# SparkFun_TC78H670FTG_Breakout.net
KiCad netlist of a schematic drawn in EAGLE
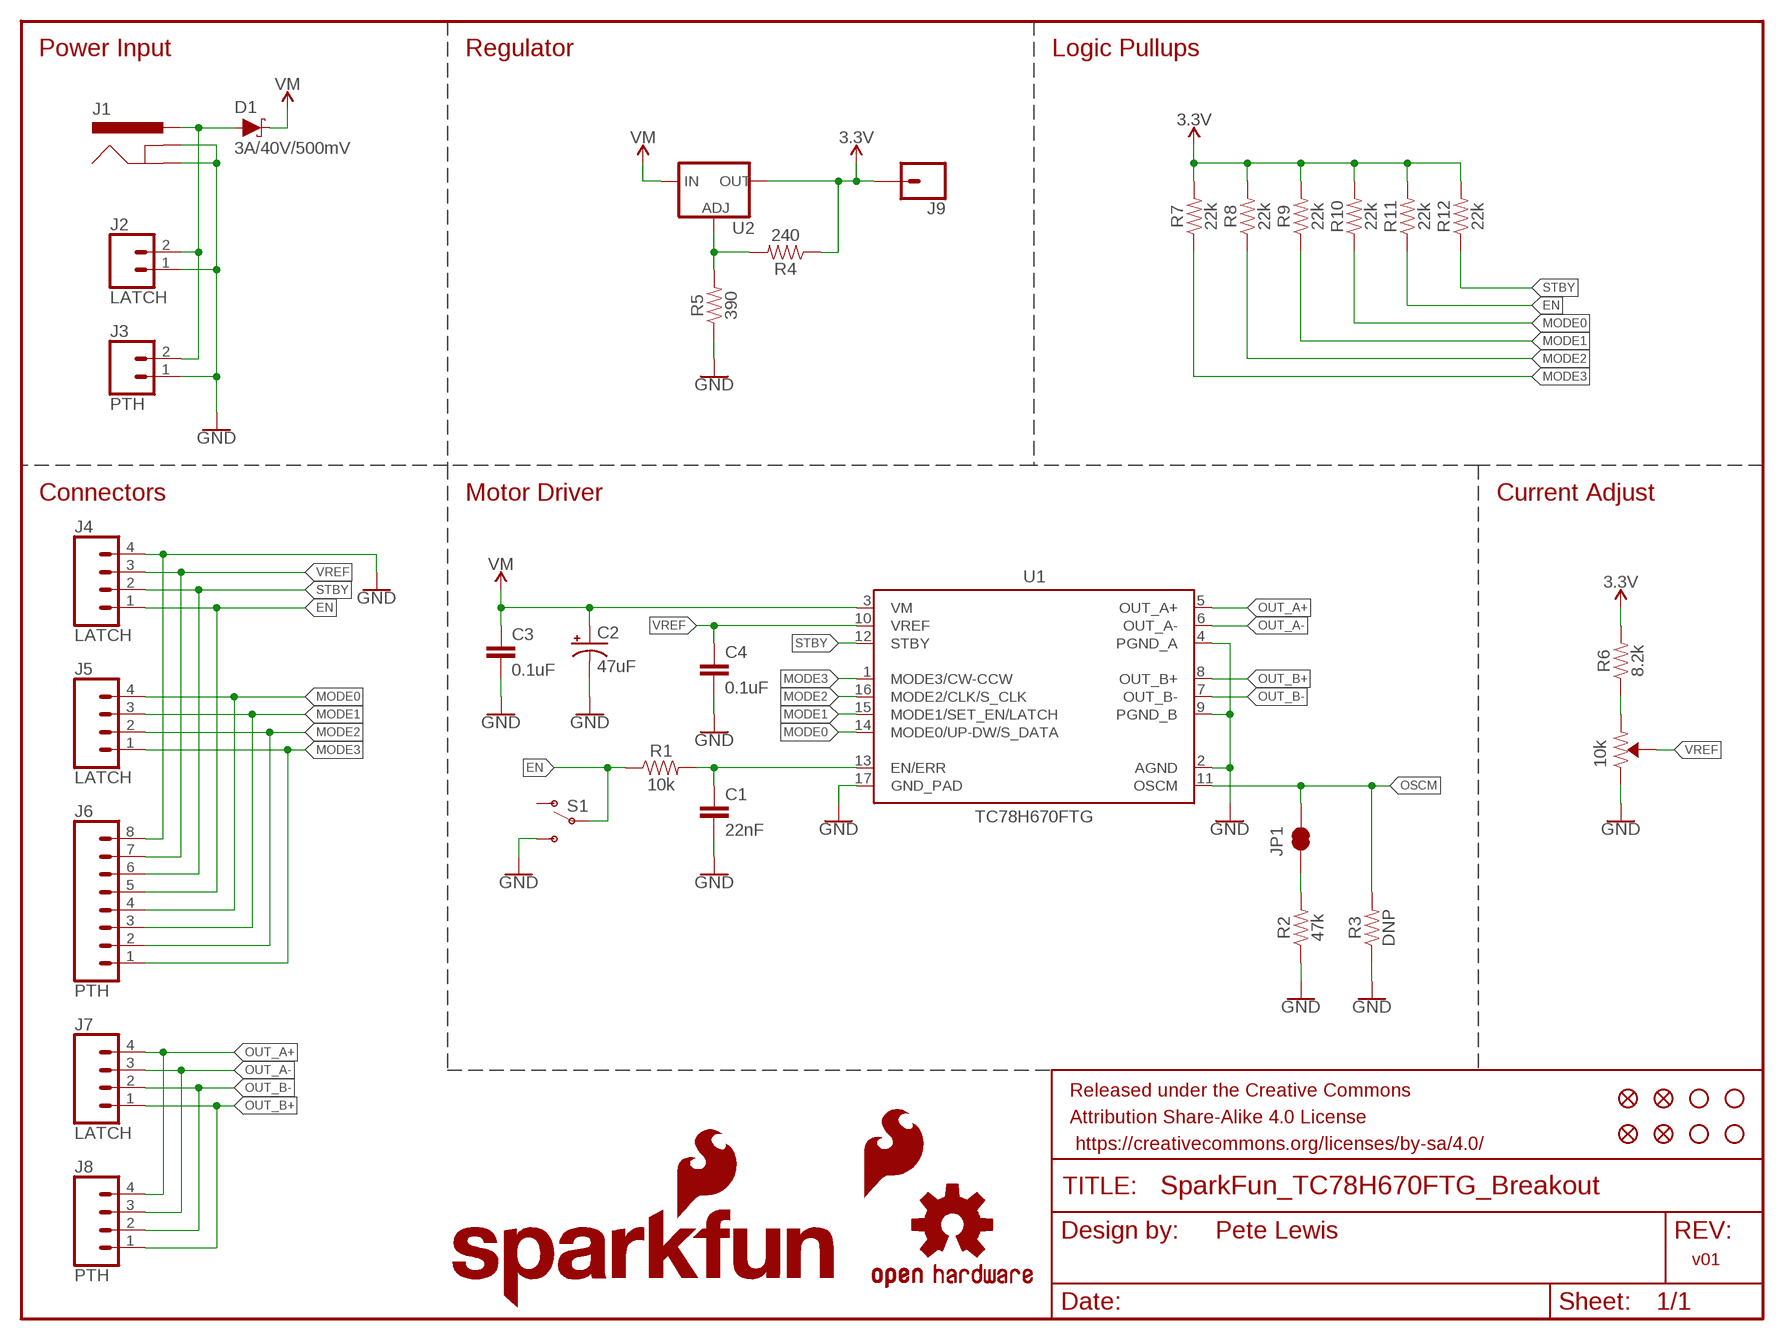
[diagram p0: schematic, sheet 1]

(export (version "E")
  (design (tool "Eeschema 10.0.6"))
  (components
    (comp (ref "C1")
      (value "22nF")
      (footprint "eagle-import:0603")
      (libsource (lib "eagle-import") (part "22NF/22,000PF-0603-50V-10%"))
    )
    (comp (ref "C2")
      (value "47uF")
      (footprint "eagle-import:PANASONIC_D")
      (libsource (lib "eagle-import") (part "47UF-POLAR-PANASONIC_D-35V-20%"))
    )
    (comp (ref "C3")
      (value "0.1uF")
      (footprint "eagle-import:0603")
      (libsource (lib "eagle-import") (part "0.1UF-0603-25V-(+80/-20%)"))
    )
    (comp (ref "C4")
      (value "0.1uF")
      (footprint "eagle-import:0603")
      (libsource (lib "eagle-import") (part "0.1UF-0603-25V-(+80/-20%)"))
    )
    (comp (ref "D1")
      (value "3A/40V/500mV")
      (footprint "eagle-import:SMA-DIODE")
      (libsource (lib "eagle-import") (part "DIODE-SCHOTTKY-B340A"))
    )
    (comp (ref "FID1")
      (value "FIDUCIAL1X2")
      (footprint "eagle-import:FIDUCIAL-1X2")
      (libsource (lib "eagle-import") (part "FIDUCIAL1X2"))
    )
    (comp (ref "FID2")
      (value "FIDUCIAL1X2")
      (footprint "eagle-import:FIDUCIAL-1X2")
      (libsource (lib "eagle-import") (part "FIDUCIAL1X2"))
    )
    (comp (ref "FID3")
      (value "FIDUCIAL1X2")
      (footprint "eagle-import:FIDUCIAL-1X2")
      (libsource (lib "eagle-import") (part "FIDUCIAL1X2"))
    )
    (comp (ref "FID4")
      (value "FIDUCIAL1X2")
      (footprint "eagle-import:FIDUCIAL-1X2")
      (libsource (lib "eagle-import") (part "FIDUCIAL1X2"))
    )
    (comp (ref "FRAME1")
      (value "FRAME-LETTER")
      (footprint "eagle-import:CREATIVE_COMMONS")
      (libsource (lib "eagle-import") (part "FRAME-LETTER"))
    )
    (comp (ref "J1")
      (value "POWER_JACKTOE")
      (footprint "eagle-import:POWER_JACK_SMD_OVERPASTE_TOE")
      (libsource (lib "eagle-import") (part "POWER_JACKTOE"))
    )
    (comp (ref "J2")
      (value "LATCH")
      (footprint "eagle-import:LATCHTERMINAL-5MM-2")
      (libsource (lib "eagle-import") (part "CONN_02LATCH_2"))
    )
    (comp (ref "J3")
      (value "PTH")
      (footprint "eagle-import:1X02_NO_SILK")
      (libsource (lib "eagle-import") (part "CONN_021X02_NO_SILK"))
    )
    (comp (ref "J4")
      (value "LATCH")
      (footprint "eagle-import:LATCHTERMINAL-5MM-4")
      (libsource (lib "eagle-import") (part "CONN_04LATCH"))
    )
    (comp (ref "J5")
      (value "LATCH")
      (footprint "eagle-import:LATCHTERMINAL-5MM-4")
      (libsource (lib "eagle-import") (part "CONN_04LATCH"))
    )
    (comp (ref "J6")
      (value "PTH")
      (footprint "eagle-import:1X08_NO_SILK")
      (libsource (lib "eagle-import") (part "CONN_08NO_SILK_FEMALE_PTH"))
    )
    (comp (ref "J7")
      (value "LATCH")
      (footprint "eagle-import:LATCHTERMINAL-5MM-4")
      (libsource (lib "eagle-import") (part "CONN_04LATCH"))
    )
    (comp (ref "J8")
      (value "PTH")
      (footprint "eagle-import:1X04_NO_SILK")
      (libsource (lib "eagle-import") (part "CONN_041X04_NO_SILK"))
    )
    (comp (ref "J9")
      (value "CONN_01PTH_NO_SILK_YES_STOP")
      (footprint "eagle-import:1X01_NO_SILK")
      (libsource (lib "eagle-import") (part "CONN_01PTH_NO_SILK_YES_STOP"))
    )
    (comp (ref "JP1")
      (value "JUMPER-SMT_2_NC_TRACE_SILK")
      (footprint "eagle-import:SMT-JUMPER_2_NC_TRACE_SILK")
      (libsource (lib "eagle-import") (part "JUMPER-SMT_2_NC_TRACE_SILK"))
    )
    (comp (ref "LOGO1")
      (value "SFE_LOGO_NAME_FLAME.1_INCH")
      (footprint "eagle-import:SFE_LOGO_NAME_FLAME_.1")
      (libsource (lib "eagle-import") (part "SFE_LOGO_NAME_FLAME.1_INCH"))
    )
    (comp (ref "LOGO2")
      (value "OSHW-LOGOS")
      (footprint "eagle-import:OSHW-LOGO-S")
      (libsource (lib "eagle-import") (part "OSHW-LOGOS"))
    )
    (comp (ref "LOGO4")
      (value "SFE_LOGO_FLAME.1_INCH")
      (footprint "eagle-import:SFE_LOGO_FLAME_.1")
      (libsource (lib "eagle-import") (part "SFE_LOGO_FLAME.1_INCH"))
    )
    (comp (ref "R1")
      (value "10k")
      (footprint "eagle-import:0603")
      (libsource (lib "eagle-import") (part "10KOHM-0603-1/10W-1%"))
    )
    (comp (ref "R2")
      (value "47k")
      (footprint "eagle-import:0603")
      (libsource (lib "eagle-import") (part "47KOHM-0603-1/10W-1%"))
    )
    (comp (ref "R3")
      (value "DNP")
      (footprint "eagle-import:AXIAL-0.3")
      (libsource (lib "eagle-import") (part "RESISTORAXIAL-0.3"))
    )
    (comp (ref "R4")
      (value "240")
      (footprint "eagle-import:0603")
      (libsource (lib "eagle-import") (part "240OHM-0603-1/10W-1%"))
    )
    (comp (ref "R5")
      (value "390")
      (footprint "eagle-import:0603")
      (libsource (lib "eagle-import") (part "390OHM-0603-1/10W-1%"))
    )
    (comp (ref "R6")
      (value "8.2k")
      (footprint "eagle-import:0603")
      (libsource (lib "eagle-import") (part "8.2KOHM-0603-1/10W-5%"))
    )
    (comp (ref "R7")
      (value "22k")
      (footprint "eagle-import:0603")
      (libsource (lib "eagle-import") (part "22KOHM-0603-1/10W-1%"))
    )
    (comp (ref "R8")
      (value "22k")
      (footprint "eagle-import:0603")
      (libsource (lib "eagle-import") (part "22KOHM-0603-1/10W-1%"))
    )
    (comp (ref "R9")
      (value "22k")
      (footprint "eagle-import:0603")
      (libsource (lib "eagle-import") (part "22KOHM-0603-1/10W-1%"))
    )
    (comp (ref "R10")
      (value "22k")
      (footprint "eagle-import:0603")
      (libsource (lib "eagle-import") (part "22KOHM-0603-1/10W-1%"))
    )
    (comp (ref "R11")
      (value "22k")
      (footprint "eagle-import:0603")
      (libsource (lib "eagle-import") (part "22KOHM-0603-1/10W-1%"))
    )
    (comp (ref "R12")
      (value "22k")
      (footprint "eagle-import:0603")
      (libsource (lib "eagle-import") (part "22KOHM-0603-1/10W-1%"))
    )
    (comp (ref "S1")
      (value "SWITCH-SPDT-PTH-11.6X4.0MM-LOCK")
      (footprint "eagle-import:SWITCH_SPDT_PTH_11.6X4.0MM_LOCK")
      (libsource (lib "eagle-import") (part "SWITCH-SPDT-PTH-11.6X4.0MM-LOCK"))
    )
    (comp (ref "STANDOFF1")
      (value "STAND-OFF")
      (footprint "eagle-import:STAND-OFF")
      (libsource (lib "eagle-import") (part "STAND-OFF"))
    )
    (comp (ref "STANDOFF2")
      (value "STAND-OFF")
      (footprint "eagle-import:STAND-OFF")
      (libsource (lib "eagle-import") (part "STAND-OFF"))
    )
    (comp (ref "STANDOFF3")
      (value "STAND-OFF")
      (footprint "eagle-import:STAND-OFF")
      (libsource (lib "eagle-import") (part "STAND-OFF"))
    )
    (comp (ref "STANDOFF4")
      (value "STAND-OFF")
      (footprint "eagle-import:STAND-OFF")
      (libsource (lib "eagle-import") (part "STAND-OFF"))
    )
    (comp (ref "U1")
      (value "TC78H670FTG")
      (footprint "eagle-import:P-VQFN16-0303-0.50-001")
      (libsource (lib "eagle-import") (part "TC78H670FTG"))
    )
    (comp (ref "U2")
      (value "V_REG_LM1117SOT223")
      (footprint "eagle-import:SOT223")
      (libsource (lib "eagle-import") (part "V_REG_LM1117SOT223"))
    )
    (comp (ref "VR1")
      (value "10k")
      (footprint "eagle-import:TRIMPOT-SMD-3MM-CLOSED")
      (libsource (lib "eagle-import") (part "TRIMPOT-SMD-3MM-CLOSED-1/8W-20%"))
    )
  )
  (nets
    (net (code "1") (name "3.3V") (class "Default")
      (node (ref "J9") (pin "1") (pinfunction "1_1") (pintype "passive"))
      (node (ref "R10") (pin "2") (pinfunction "2_2") (pintype "passive"))
      (node (ref "R11") (pin "2") (pinfunction "2_2") (pintype "passive"))
      (node (ref "R12") (pin "2") (pinfunction "2_2") (pintype "passive"))
      (node (ref "R4") (pin "1") (pinfunction "1_1") (pintype "passive"))
      (node (ref "R6") (pin "2") (pinfunction "2_2") (pintype "passive"))
      (node (ref "R7") (pin "2") (pinfunction "2_2") (pintype "passive"))
      (node (ref "R8") (pin "2") (pinfunction "2_2") (pintype "passive"))
      (node (ref "R9") (pin "2") (pinfunction "2_2") (pintype "passive"))
      (node (ref "U2") (pin "2") (pinfunction "OUT_2") (pintype "output"))
      (node (ref "U2") (pin "4") (pinfunction "OUT_4") (pintype "output"))
    )
    (net (code "2") (name "EN") (class "Default")
      (node (ref "J4") (pin "1") (pinfunction "1_1") (pintype "passive"))
      (node (ref "J6") (pin "5") (pinfunction "5_5") (pintype "passive"))
      (node (ref "R1") (pin "1") (pinfunction "1_1") (pintype "passive"))
      (node (ref "R11") (pin "1") (pinfunction "1_1") (pintype "passive"))
      (node (ref "S1") (pin "2") (pinfunction "P_2") (pintype "passive"))
    )
    (net (code "3") (name "GND") (class "Default")
      (node (ref "C1") (pin "2") (pinfunction "2_2") (pintype "passive"))
      (node (ref "C2") (pin "-") (pinfunction "-_-") (pintype "passive"))
      (node (ref "C3") (pin "2") (pinfunction "2_2") (pintype "passive"))
      (node (ref "C4") (pin "2") (pinfunction "2_2") (pintype "passive"))
      (node (ref "J1") (pin "GND") (pinfunction "GNDBREAK_GND") (pintype "bidirectional"))
      (node (ref "J1") (pin "P$4") (pinfunction "GND_P$4") (pintype "bidirectional"))
      (node (ref "J2") (pin "1") (pinfunction "1_1") (pintype "passive"))
      (node (ref "J3") (pin "1") (pinfunction "1_1") (pintype "passive"))
      (node (ref "J4") (pin "4") (pinfunction "4_4") (pintype "passive"))
      (node (ref "J6") (pin "8") (pinfunction "8_8") (pintype "passive"))
      (node (ref "R2") (pin "1") (pinfunction "1_1") (pintype "passive"))
      (node (ref "R3") (pin "P$1") (pinfunction "1_P$1") (pintype "passive"))
      (node (ref "R5") (pin "1") (pinfunction "1_1") (pintype "passive"))
      (node (ref "S1") (pin "3") (pinfunction "S_3") (pintype "passive"))
      (node (ref "U1") (pin "17") (pinfunction "GND_PAD_17") (pintype "bidirectional"))
      (node (ref "U1") (pin "2") (pinfunction "AGND_2") (pintype "bidirectional"))
      (node (ref "U1") (pin "4") (pinfunction "PGND_A_4") (pintype "bidirectional"))
      (node (ref "U1") (pin "9") (pinfunction "PGND_B_9") (pintype "bidirectional"))
      (node (ref "VR1") (pin "3") (pinfunction "CW_3") (pintype "passive"))
    )
    (net (code "4") (name "MODE0") (class "Default")
      (node (ref "J5") (pin "4") (pinfunction "4_4") (pintype "passive"))
      (node (ref "J6") (pin "4") (pinfunction "4_4") (pintype "passive"))
      (node (ref "R10") (pin "1") (pinfunction "1_1") (pintype "passive"))
      (node (ref "U1") (pin "14") (pinfunction "MODE0/UP-DW/S_DATA_14") (pintype "bidirectional"))
    )
    (net (code "5") (name "MODE1") (class "Default")
      (node (ref "J5") (pin "3") (pinfunction "3_3") (pintype "passive"))
      (node (ref "J6") (pin "3") (pinfunction "3_3") (pintype "passive"))
      (node (ref "R9") (pin "1") (pinfunction "1_1") (pintype "passive"))
      (node (ref "U1") (pin "15") (pinfunction "MODE1/SET_EN/LATCH_15") (pintype "bidirectional"))
    )
    (net (code "6") (name "MODE2") (class "Default")
      (node (ref "J5") (pin "2") (pinfunction "2_2") (pintype "passive"))
      (node (ref "J6") (pin "2") (pinfunction "2_2") (pintype "passive"))
      (node (ref "R8") (pin "1") (pinfunction "1_1") (pintype "passive"))
      (node (ref "U1") (pin "16") (pinfunction "MODE2/CLK/S_CLK_16") (pintype "bidirectional"))
    )
    (net (code "7") (name "MODE3") (class "Default")
      (node (ref "J5") (pin "1") (pinfunction "1_1") (pintype "passive"))
      (node (ref "J6") (pin "1") (pinfunction "1_1") (pintype "passive"))
      (node (ref "R7") (pin "1") (pinfunction "1_1") (pintype "passive"))
      (node (ref "U1") (pin "1") (pinfunction "MODE3/CW-CCW_1") (pintype "bidirectional"))
    )
    (net (code "8") (name "Net-(J1-PWR)") (class "Default")
      (node (ref "D1") (pin "A") (pinfunction "A_A") (pintype "passive"))
      (node (ref "J1") (pin "VIN0") (pinfunction "PWR_VIN0") (pintype "bidirectional"))
      (node (ref "J2") (pin "2") (pinfunction "2_2") (pintype "passive"))
      (node (ref "J3") (pin "2") (pinfunction "2_2") (pintype "passive"))
    )
    (net (code "9") (name "Net-(JP1-Pad1)") (class "Default")
      (node (ref "JP1") (pin "1") (pinfunction "1_1") (pintype "passive"))
      (node (ref "R2") (pin "2") (pinfunction "2_2") (pintype "passive"))
    )
    (net (code "10") (name "Net-(U1-EN{slash}ERR)") (class "Default")
      (node (ref "C1") (pin "1") (pinfunction "1_1") (pintype "passive"))
      (node (ref "R1") (pin "2") (pinfunction "2_2") (pintype "passive"))
      (node (ref "U1") (pin "13") (pinfunction "EN/ERR_13") (pintype "bidirectional"))
    )
    (net (code "11") (name "Net-(U2-ADJ)") (class "Default")
      (node (ref "R4") (pin "2") (pinfunction "2_2") (pintype "passive"))
      (node (ref "R5") (pin "2") (pinfunction "2_2") (pintype "passive"))
      (node (ref "U2") (pin "1") (pinfunction "ADJ_1") (pintype "input"))
    )
    (net (code "12") (name "Net-(VR1-CCW)") (class "Default")
      (node (ref "R6") (pin "1") (pinfunction "1_1") (pintype "passive"))
      (node (ref "VR1") (pin "1") (pinfunction "CCW_1") (pintype "passive"))
    )
    (net (code "13") (name "OSCM") (class "Default")
      (node (ref "JP1") (pin "2") (pinfunction "2_2") (pintype "passive"))
      (node (ref "R3") (pin "P$2") (pinfunction "2_P$2") (pintype "passive"))
      (node (ref "U1") (pin "11") (pinfunction "OSCM_11") (pintype "bidirectional"))
    )
    (net (code "14") (name "OUT_A+") (class "Default")
      (node (ref "J7") (pin "4") (pinfunction "4_4") (pintype "passive"))
      (node (ref "J8") (pin "4") (pinfunction "4_4") (pintype "passive"))
      (node (ref "U1") (pin "5") (pinfunction "OUT_A+_5") (pintype "bidirectional"))
    )
    (net (code "15") (name "OUT_A-") (class "Default")
      (node (ref "J7") (pin "3") (pinfunction "3_3") (pintype "passive"))
      (node (ref "J8") (pin "3") (pinfunction "3_3") (pintype "passive"))
      (node (ref "U1") (pin "6") (pinfunction "OUT_A-_6") (pintype "bidirectional"))
    )
    (net (code "16") (name "OUT_B+") (class "Default")
      (node (ref "J7") (pin "1") (pinfunction "1_1") (pintype "passive"))
      (node (ref "J8") (pin "1") (pinfunction "1_1") (pintype "passive"))
      (node (ref "U1") (pin "8") (pinfunction "OUT_B+_8") (pintype "bidirectional"))
    )
    (net (code "17") (name "OUT_B-") (class "Default")
      (node (ref "J7") (pin "2") (pinfunction "2_2") (pintype "passive"))
      (node (ref "J8") (pin "2") (pinfunction "2_2") (pintype "passive"))
      (node (ref "U1") (pin "7") (pinfunction "OUT_B-_7") (pintype "bidirectional"))
    )
    (net (code "18") (name "STBY") (class "Default")
      (node (ref "J4") (pin "2") (pinfunction "2_2") (pintype "passive"))
      (node (ref "J6") (pin "6") (pinfunction "6_6") (pintype "passive"))
      (node (ref "R12") (pin "1") (pinfunction "1_1") (pintype "passive"))
      (node (ref "U1") (pin "12") (pinfunction "STBY_12") (pintype "bidirectional"))
    )
    (net (code "19") (name "VM") (class "Default")
      (node (ref "C2") (pin "+") (pinfunction "+_+") (pintype "passive"))
      (node (ref "C3") (pin "1") (pinfunction "1_1") (pintype "passive"))
      (node (ref "D1") (pin "C") (pinfunction "C_C") (pintype "passive"))
      (node (ref "U1") (pin "3") (pinfunction "VM_3") (pintype "bidirectional"))
      (node (ref "U2") (pin "3") (pinfunction "IN_3") (pintype "input"))
    )
    (net (code "20") (name "VREF") (class "Default")
      (node (ref "C4") (pin "1") (pinfunction "1_1") (pintype "passive"))
      (node (ref "J4") (pin "3") (pinfunction "3_3") (pintype "passive"))
      (node (ref "J6") (pin "7") (pinfunction "7_7") (pintype "passive"))
      (node (ref "U1") (pin "10") (pinfunction "VREF_10") (pintype "bidirectional"))
      (node (ref "VR1") (pin "2") (pinfunction "WIPER_2") (pintype "passive"))
    )
    (net (code "21") (name "unconnected-(S1-O-Pad1)") (class "Default")
      (node (ref "S1") (pin "1") (pinfunction "O_1") (pintype "passive"))
    )
  )
)
